# sx-rj45-verteiler-m-einspeisung.net
KiCad netlist of a schematic drawn in EAGLE
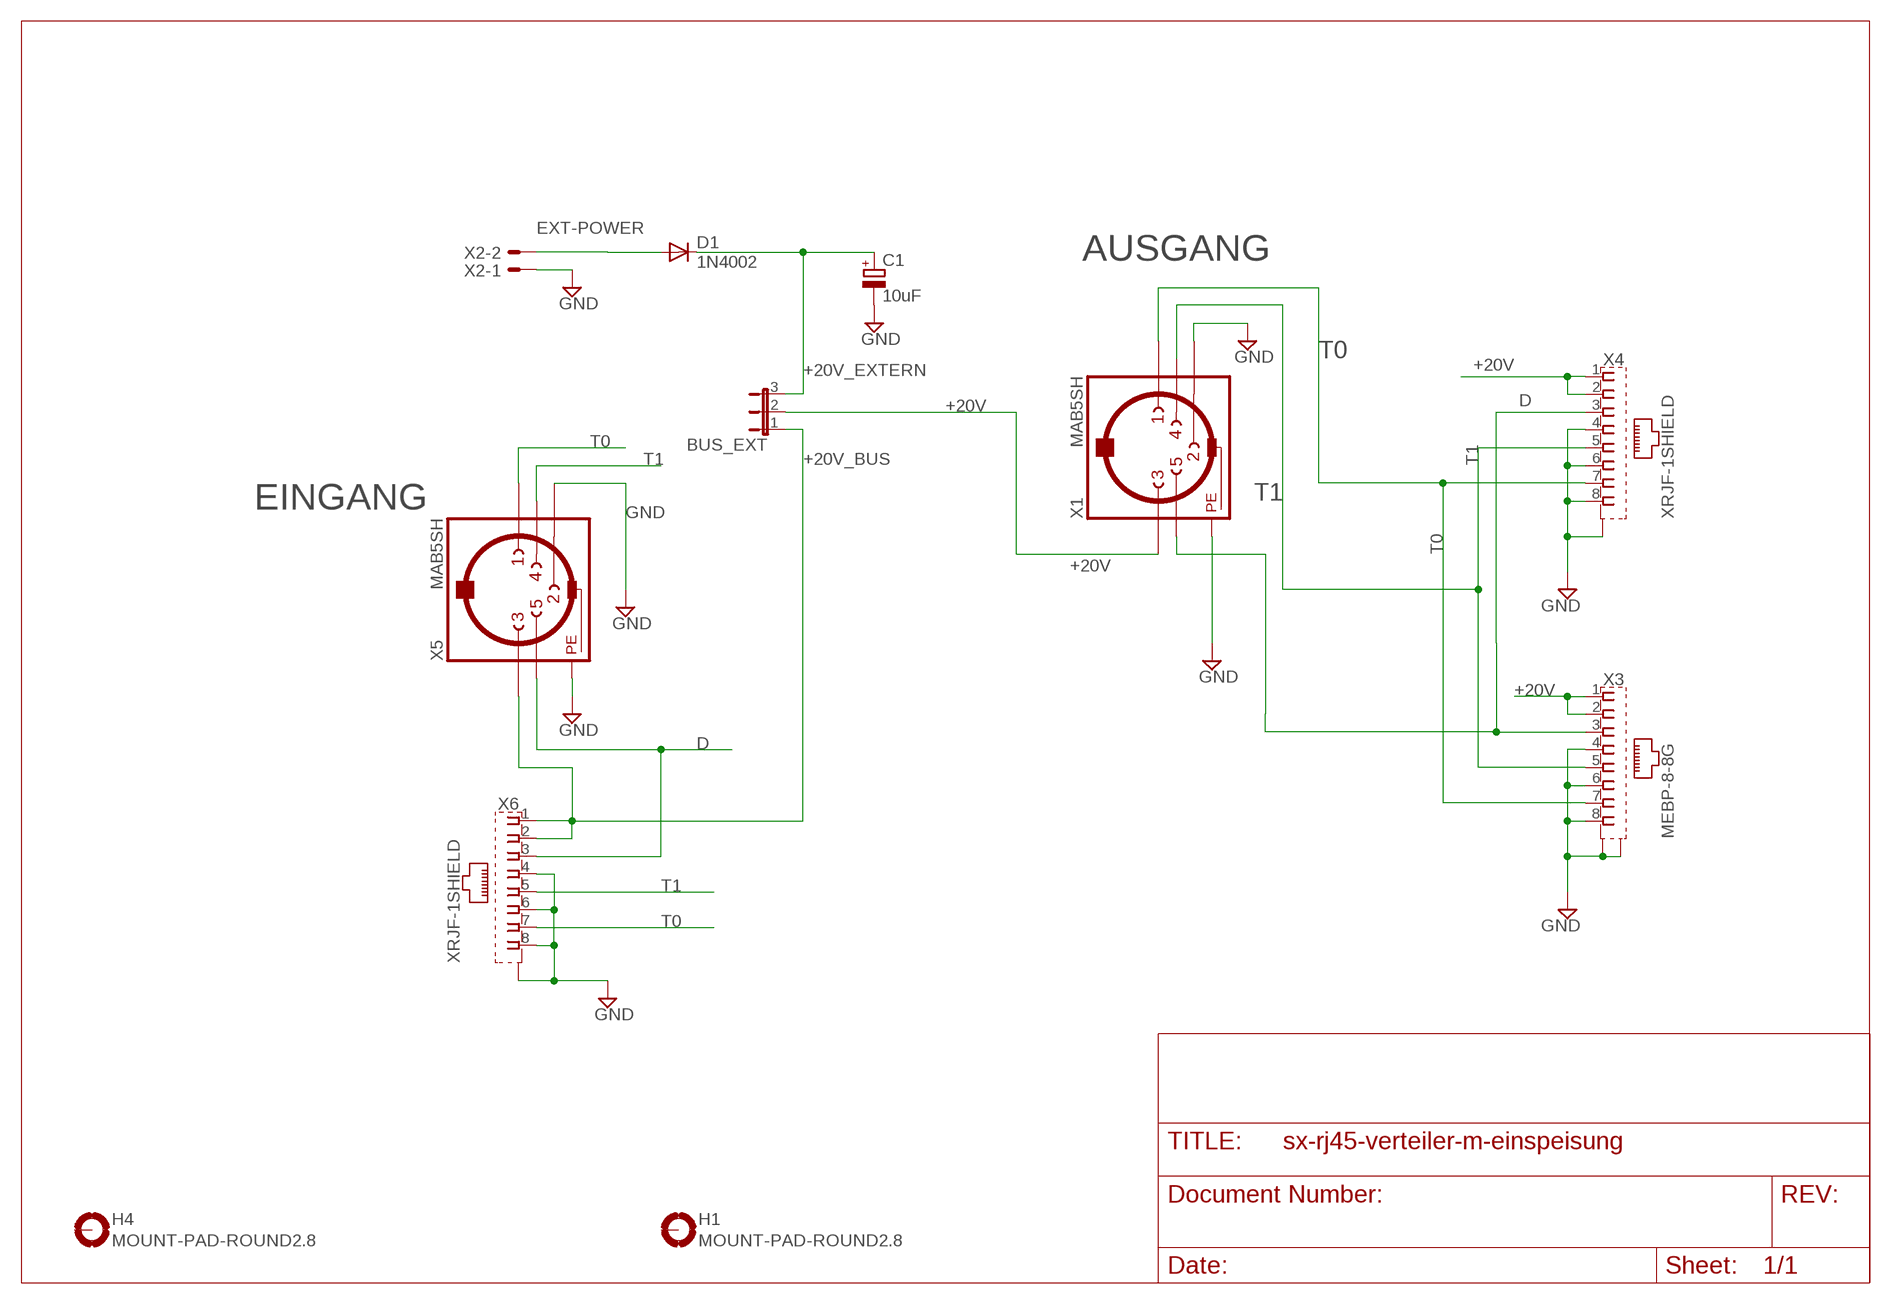
[diagram p0: schematic, sheet 1]

(export (version "E")
  (design (tool "Eeschema 10.0.6"))
  (components
    (comp (ref "BUS_EXT")
      (value "JP2E")
      (footprint "eagle-import:JP2")
      (libsource (lib "eagle-import") (part "JP2E"))
    )
    (comp (ref "C1")
      (value "10uF")
      (footprint "eagle-import:E2,5-7")
      (libsource (lib "eagle-import") (part "CPOL-EUE2.5-7"))
    )
    (comp (ref "D1")
      (value "1N4002")
      (footprint "eagle-import:DO201-15")
      (libsource (lib "eagle-import") (part "DIODE-DO201-15"))
    )
    (comp (ref "H1")
      (value "MOUNT-PAD-ROUND2.8")
      (footprint "eagle-import:2,8-PAD")
      (libsource (lib "eagle-import") (part "MOUNT-PAD-ROUND2.8"))
    )
    (comp (ref "H4")
      (value "MOUNT-PAD-ROUND2.8")
      (footprint "eagle-import:2,8-PAD")
      (libsource (lib "eagle-import") (part "MOUNT-PAD-ROUND2.8"))
    )
    (comp (ref "X1")
      (value "MAB5SH")
      (footprint "eagle-import:MAB5SH")
      (libsource (lib "eagle-import") (part "MAB5SH"))
    )
    (comp (ref "X2")
      (value "AKL18X-02W")
      (footprint "eagle-import:AKL182-02")
      (libsource (lib "eagle-import") (part "AKL18X-02W"))
    )
    (comp (ref "X3")
      (value "MEBP-8-8G")
      (footprint "eagle-import:XRJF-01A-0-D2A-010")
      (libsource (lib "eagle-import") (part "XRJFMEBP-8-8G-01A-0-D2A-010"))
    )
    (comp (ref "X4")
      (value "XRJF-1SHIELD")
      (footprint "eagle-import:XRJF-01A-OHNE_LOCH")
      (libsource (lib "eagle-import") (part "XRJF-1SHIELD"))
    )
    (comp (ref "X5")
      (value "MAB5SH")
      (footprint "eagle-import:MAB5SH")
      (libsource (lib "eagle-import") (part "MAB5SH"))
    )
    (comp (ref "X6")
      (value "XRJF-1SHIELD")
      (footprint "eagle-import:XRJF-01A-OHNE_LOCH")
      (libsource (lib "eagle-import") (part "XRJF-1SHIELD"))
    )
  )
  (nets
    (net (code "1") (name "/+20V") (class "Default")
      (node (ref "BUS_EXT") (pin "2") (pinfunction "2_2") (pintype "passive"))
      (node (ref "X1") (pin "3") (pinfunction "3_3") (pintype "passive"))
      (node (ref "X3") (pin "1") (pinfunction "1_1") (pintype "passive"))
      (node (ref "X3") (pin "2") (pinfunction "2_2") (pintype "passive"))
      (node (ref "X4") (pin "1") (pinfunction "1_1") (pintype "passive"))
      (node (ref "X4") (pin "2") (pinfunction "2_2") (pintype "passive"))
    )
    (net (code "2") (name "/+20V_BUS") (class "Default")
      (node (ref "BUS_EXT") (pin "1") (pinfunction "1_1") (pintype "passive"))
      (node (ref "X5") (pin "3") (pinfunction "3_3") (pintype "passive"))
      (node (ref "X6") (pin "1") (pinfunction "1_1") (pintype "passive"))
      (node (ref "X6") (pin "2") (pinfunction "2_2") (pintype "passive"))
    )
    (net (code "3") (name "/+20V_EXTERN") (class "Default")
      (node (ref "BUS_EXT") (pin "3") (pinfunction "3_3") (pintype "passive"))
      (node (ref "C1") (pin "+") (pinfunction "+_+") (pintype "passive"))
      (node (ref "D1") (pin "C") (pinfunction "C_C") (pintype "passive"))
    )
    (net (code "4") (name "/D") (class "Default")
      (node (ref "X1") (pin "5") (pinfunction "5_5") (pintype "passive"))
      (node (ref "X3") (pin "3") (pinfunction "3_3") (pintype "passive"))
      (node (ref "X4") (pin "3") (pinfunction "3_3") (pintype "passive"))
      (node (ref "X5") (pin "5") (pinfunction "5_5") (pintype "passive"))
      (node (ref "X6") (pin "3") (pinfunction "3_3") (pintype "passive"))
    )
    (net (code "5") (name "/EXT-POWER") (class "Default")
      (node (ref "D1") (pin "A") (pinfunction "A_A") (pintype "passive"))
      (node (ref "X2") (pin "P$2") (pinfunction "S_P$2") (pintype "passive"))
    )
    (net (code "6") (name "/T0") (class "Default")
      (node (ref "X1") (pin "1") (pinfunction "1_1") (pintype "passive"))
      (node (ref "X3") (pin "7") (pinfunction "7_7") (pintype "passive"))
      (node (ref "X4") (pin "7") (pinfunction "7_7") (pintype "passive"))
      (node (ref "X5") (pin "1") (pinfunction "1_1") (pintype "passive"))
      (node (ref "X6") (pin "7") (pinfunction "7_7") (pintype "passive"))
    )
    (net (code "7") (name "/T1") (class "Default")
      (node (ref "X1") (pin "4") (pinfunction "4_4") (pintype "passive"))
      (node (ref "X3") (pin "5") (pinfunction "5_5") (pintype "passive"))
      (node (ref "X4") (pin "5") (pinfunction "5_5") (pintype "passive"))
      (node (ref "X5") (pin "4") (pinfunction "4_4") (pintype "passive"))
      (node (ref "X6") (pin "5") (pinfunction "5_5") (pintype "passive"))
    )
    (net (code "8") (name "GND") (class "Default")
      (node (ref "C1") (pin "-") (pinfunction "-_-") (pintype "passive"))
      (node (ref "X1") (pin "2") (pinfunction "2_2") (pintype "passive"))
      (node (ref "X1") (pin "PE") (pinfunction "PE_PE") (pintype "power_in"))
      (node (ref "X1") (pin "PE1") (pinfunction "PE_PE1") (pintype "power_in"))
      (node (ref "X1") (pin "PE@") (pinfunction "PE_PE@") (pintype "power_in"))
      (node (ref "X1") (pin "PE@1") (pinfunction "PE_PE@1") (pintype "power_in"))
      (node (ref "X2") (pin "P$1") (pinfunction "S_P$1") (pintype "passive"))
      (node (ref "X3") (pin "4") (pinfunction "4_4") (pintype "passive"))
      (node (ref "X3") (pin "6") (pinfunction "6_6") (pintype "passive"))
      (node (ref "X3") (pin "8") (pinfunction "8_8") (pintype "passive"))
      (node (ref "X3") (pin "S1") (pinfunction "S_S1") (pintype "passive"))
      (node (ref "X3") (pin "S2") (pinfunction "S_S2") (pintype "passive"))
      (node (ref "X4") (pin "4") (pinfunction "4_4") (pintype "passive"))
      (node (ref "X4") (pin "6") (pinfunction "6_6") (pintype "passive"))
      (node (ref "X4") (pin "8") (pinfunction "8_8") (pintype "passive"))
      (node (ref "X4") (pin "S1") (pinfunction "S_S1") (pintype "passive"))
      (node (ref "X5") (pin "2") (pinfunction "2_2") (pintype "passive"))
      (node (ref "X5") (pin "PE") (pinfunction "PE_PE") (pintype "power_in"))
      (node (ref "X5") (pin "PE1") (pinfunction "PE_PE1") (pintype "power_in"))
      (node (ref "X5") (pin "PE@") (pinfunction "PE_PE@") (pintype "power_in"))
      (node (ref "X5") (pin "PE@1") (pinfunction "PE_PE@1") (pintype "power_in"))
      (node (ref "X6") (pin "4") (pinfunction "4_4") (pintype "passive"))
      (node (ref "X6") (pin "6") (pinfunction "6_6") (pintype "passive"))
      (node (ref "X6") (pin "8") (pinfunction "8_8") (pintype "passive"))
      (node (ref "X6") (pin "S1") (pinfunction "S_S1") (pintype "passive"))
    )
    (net (code "9") (name "unconnected-(H1-MOUNT-PadB2,8)") (class "Default")
      (node (ref "H1") (pin "B2,8") (pinfunction "MOUNT_B2,8") (pintype "passive"))
    )
    (net (code "10") (name "unconnected-(H4-MOUNT-PadB2,8)") (class "Default")
      (node (ref "H4") (pin "B2,8") (pinfunction "MOUNT_B2,8") (pintype "passive"))
    )
  )
)
